# analog_heteroThermistor_3xChannel_R3.net
KiCad netlist of a schematic drawn in EAGLE
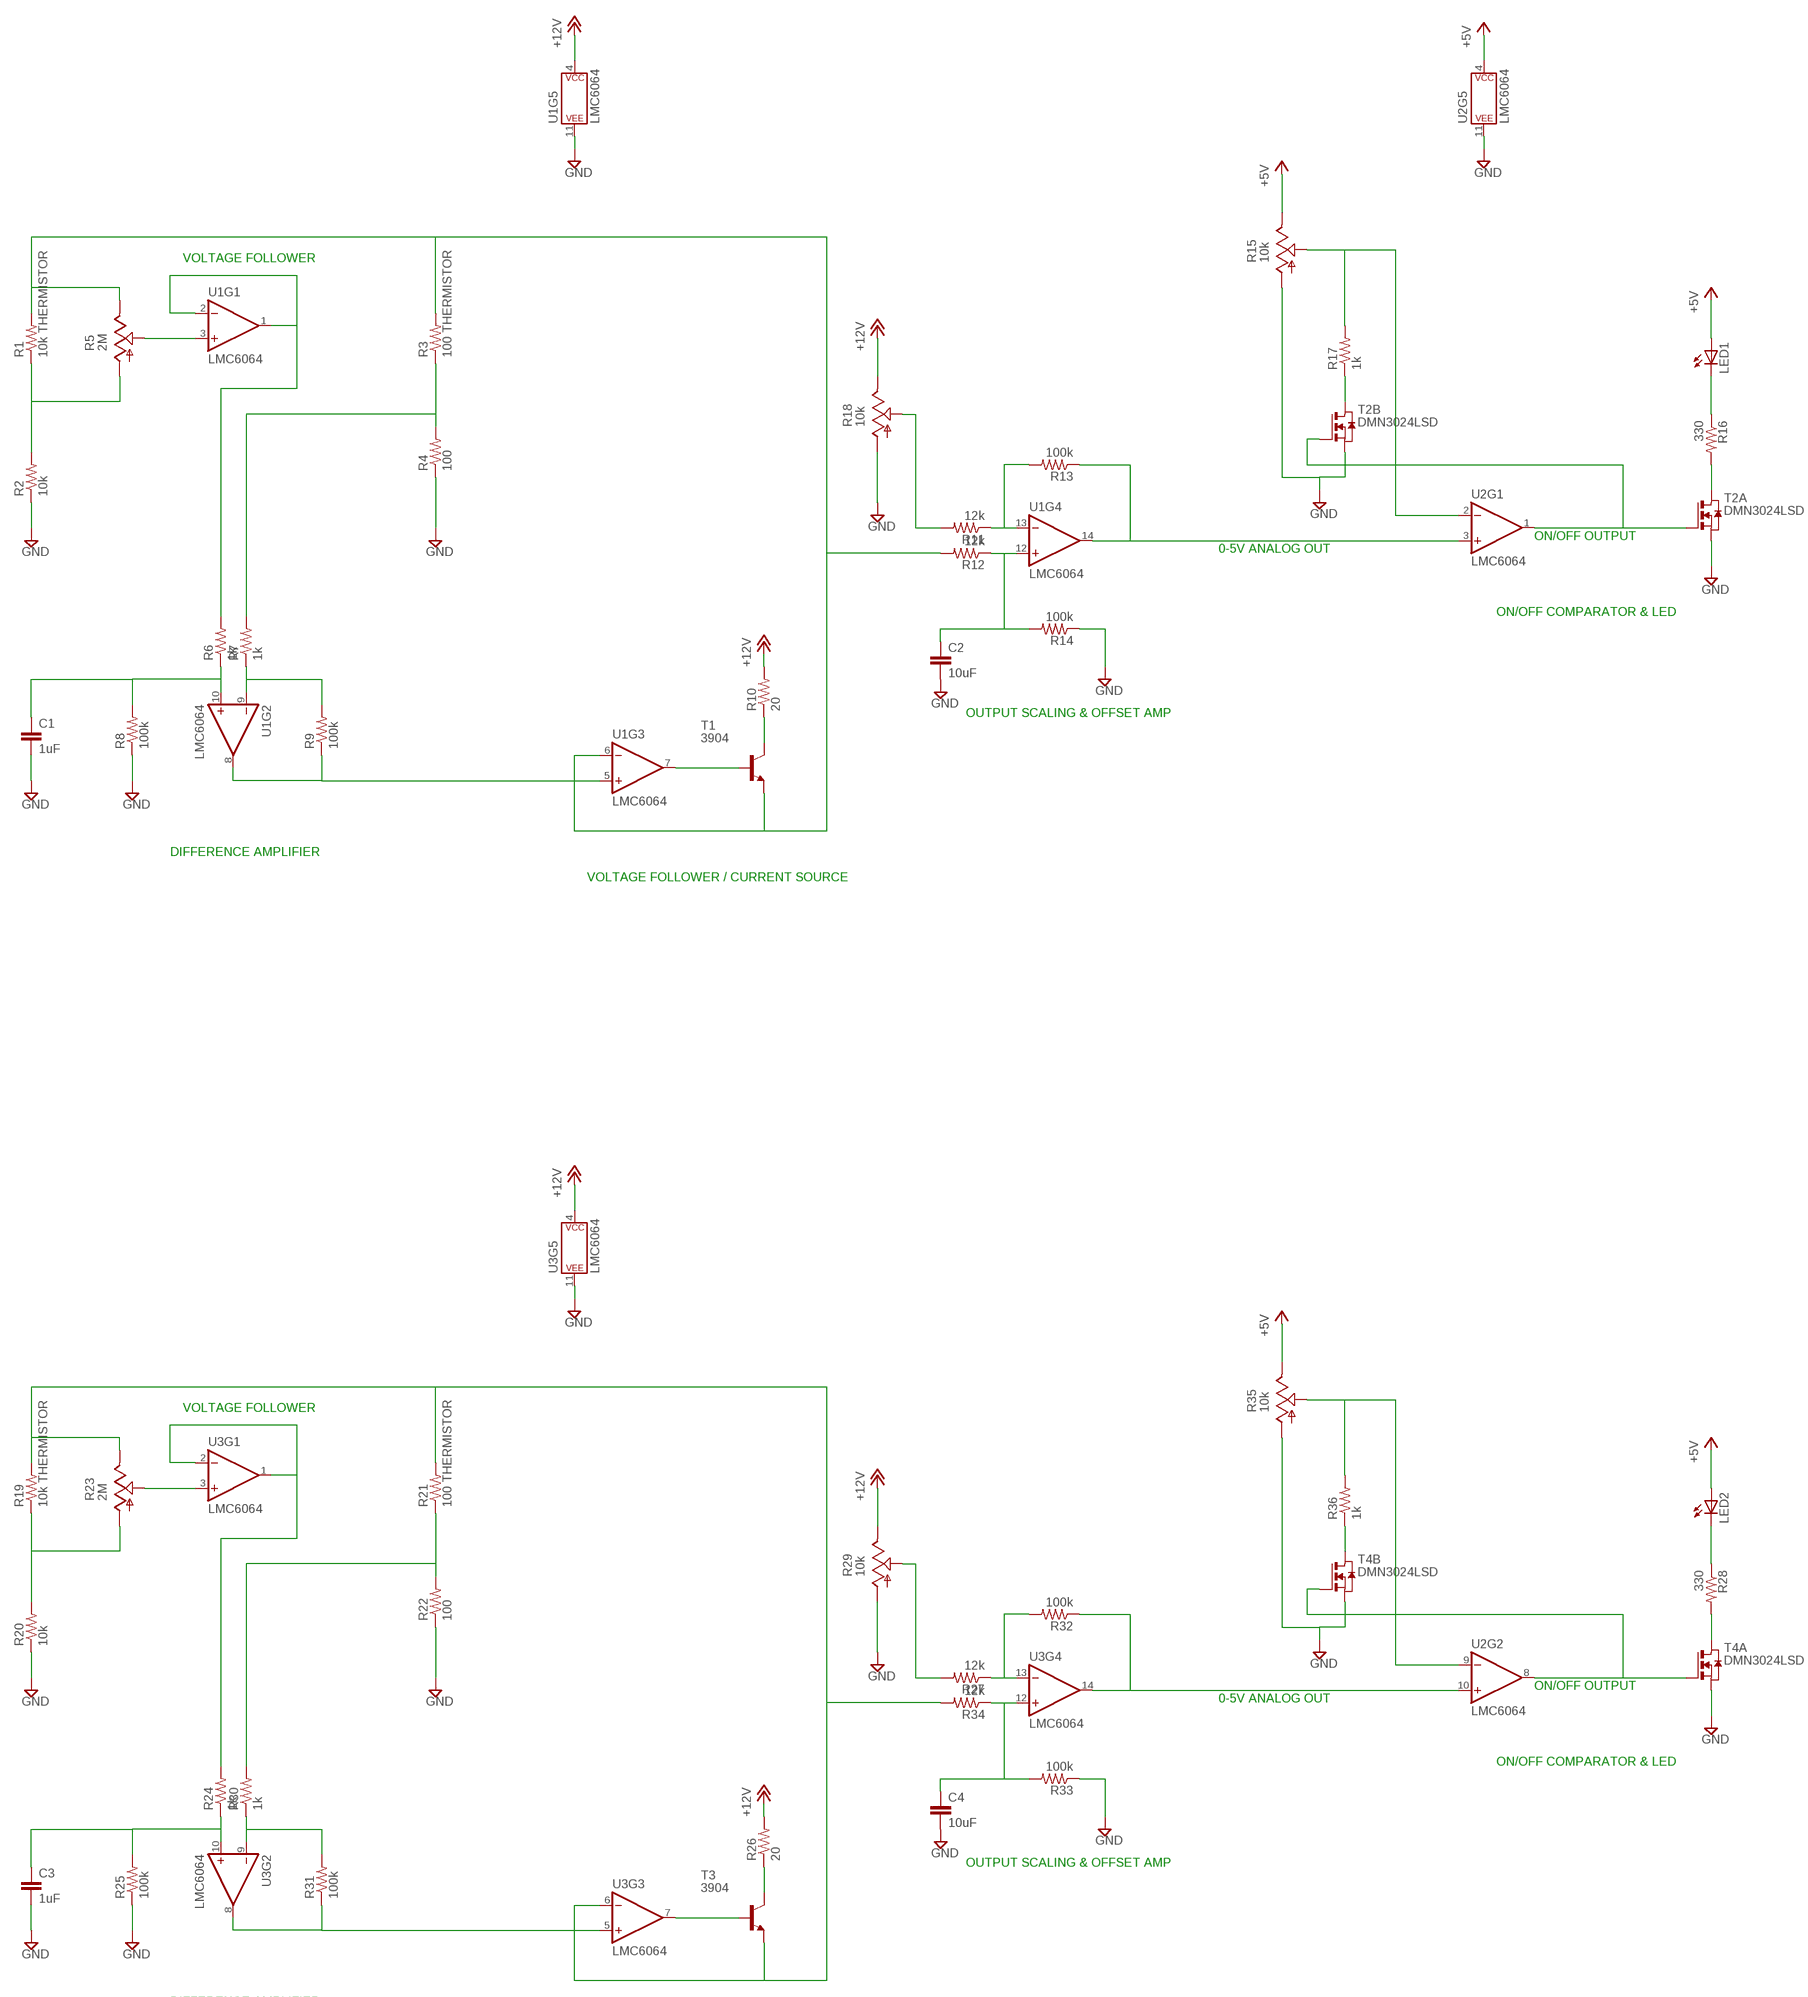
[diagram p0: schematic, sheet 1, part 1 of 2]
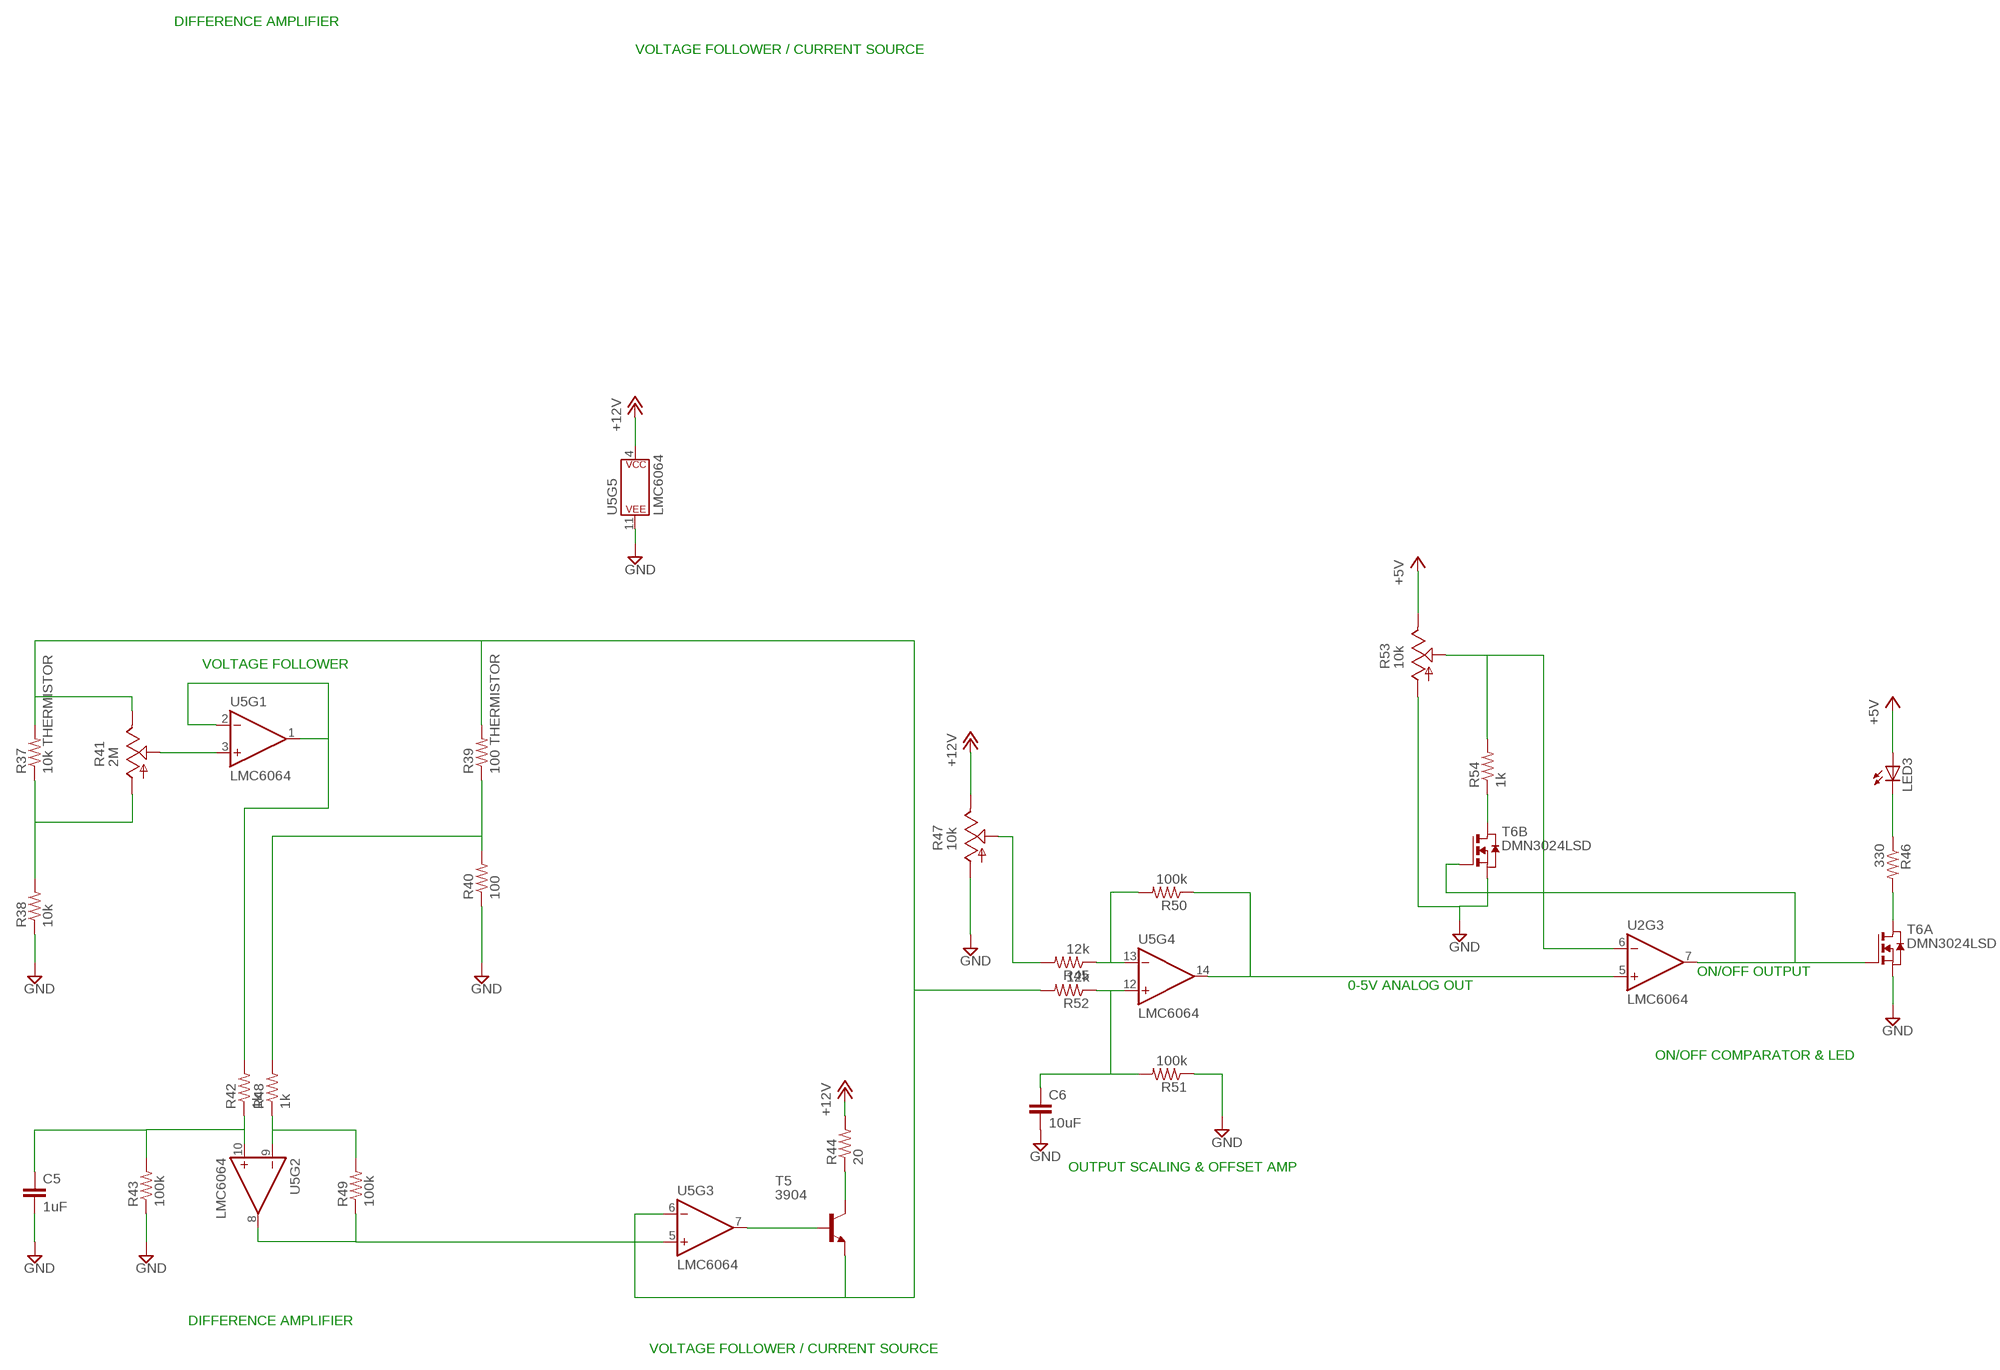
[diagram p1: schematic, sheet 1, part 2 of 2]

(export (version "E")
  (design (tool "Eeschema 10.0.6"))
  (components
    (comp (ref "C1")
      (value "1uF")
      (footprint "eagle-import:C0603")
      (fields
        (field (name "MF") "Murata Electronics North America")
        (field (name "MPN") "GRM188R61C105KA93D")
      )
      (libsource (lib "eagle-import") (part "C-EUC0603"))
    )
    (comp (ref "C2")
      (value "10uF")
      (footprint "eagle-import:C0603")
      (fields
        (field (name "MF") "Murata Electronics North America")
        (field (name "MPN") "GRM188C81C106MA73D")
      )
      (libsource (lib "eagle-import") (part "C-EUC0603"))
    )
    (comp (ref "C3")
      (value "1uF")
      (footprint "eagle-import:C0603")
      (fields
        (field (name "MF") "Murata Electronics North America")
        (field (name "MPN") "GRM188R61C105KA93D")
      )
      (libsource (lib "eagle-import") (part "C-EUC0603"))
    )
    (comp (ref "C4")
      (value "10uF")
      (footprint "eagle-import:C0603")
      (fields
        (field (name "MF") "Murata Electronics North America")
        (field (name "MPN") "GRM188C81C106MA73D")
      )
      (libsource (lib "eagle-import") (part "C-EUC0603"))
    )
    (comp (ref "C5")
      (value "1uF")
      (footprint "eagle-import:C0603")
      (fields
        (field (name "MF") "Murata Electronics North America")
        (field (name "MPN") "GRM188R61C105KA93D")
      )
      (libsource (lib "eagle-import") (part "C-EUC0603"))
    )
    (comp (ref "C6")
      (value "10uF")
      (footprint "eagle-import:C0603")
      (fields
        (field (name "MF") "Murata Electronics North America")
        (field (name "MPN") "GRM188C81C106MA73D")
      )
      (libsource (lib "eagle-import") (part "C-EUC0603"))
    )
    (comp (ref "LED1")
      (value "LEDCHIPLED_1206")
      (footprint "eagle-import:CHIPLED_1206")
      (fields (field (name "MF") "Lite-On Inc.") (field (name "MPN") "LTST-C150GKT"))
      (libsource (lib "eagle-import") (part "LEDCHIPLED_1206"))
    )
    (comp (ref "LED2")
      (value "LEDCHIPLED_1206")
      (footprint "eagle-import:CHIPLED_1206")
      (fields (field (name "MF") "Lite-On Inc.") (field (name "MPN") "LTST-C150GKT"))
      (libsource (lib "eagle-import") (part "LEDCHIPLED_1206"))
    )
    (comp (ref "LED3")
      (value "LEDCHIPLED_1206")
      (footprint "eagle-import:CHIPLED_1206")
      (fields (field (name "MF") "Lite-On Inc.") (field (name "MPN") "LTST-C150GKT"))
      (libsource (lib "eagle-import") (part "LEDCHIPLED_1206"))
    )
    (comp (ref "R1")
      (value "10k THERMISTOR")
      (footprint "eagle-import:R0603")
      (fields
        (field (name "DISTR") "Digikey")
        (field (name "DISTRPN") "490-2436-1-ND")
        (field (name "MF") "Murata Electronics North America")
        (field (name "MPN") "NCP18XH103J03RB")
      )
      (libsource (lib "eagle-import") (part "R-US_R0603"))
    )
    (comp (ref "R2")
      (value "10k")
      (footprint "eagle-import:R0603")
      (fields (field (name "MF") "Panasonic Electronic Components") (field (name "MPN") "ERJ-PA3F1002V"))
      (libsource (lib "eagle-import") (part "R-US_R0603"))
    )
    (comp (ref "R3")
      (value "100 THERMISTOR")
      (footprint "eagle-import:R0603")
      (fields
        (field (name "DISTR") "Digikey")
        (field (name "DISTRPN") "490-2434-1-ND")
        (field (name "MF") "Murata Electronics North America")
        (field (name "MPN") "NCP18XF101J03RB")
      )
      (libsource (lib "eagle-import") (part "R-US_R0603"))
    )
    (comp (ref "R4")
      (value "100")
      (footprint "eagle-import:R0603")
      (fields (field (name "MF") "Panasonic Electronic Components") (field (name "MPN") "ERJ-PA3F1000V"))
      (libsource (lib "eagle-import") (part "R-US_R0603"))
    )
    (comp (ref "R5")
      (value "2M")
      (footprint "eagle-import:SM-42_43W")
      (fields (field (name "MF") "Copal Electronics Inc.") (field (name "MPN") "SM-42TW205"))
      (libsource (lib "eagle-import") (part "TRIM_US-SM-42/43W"))
    )
    (comp (ref "R6")
      (value "1k")
      (footprint "eagle-import:R0603")
      (fields (field (name "MF") "Panasonic Electronic Components") (field (name "MPN") "ERJ-PA3F1001V"))
      (libsource (lib "eagle-import") (part "R-US_R0603"))
    )
    (comp (ref "R7")
      (value "1k")
      (footprint "eagle-import:R0603")
      (fields (field (name "MF") "Panasonic Electronic Components") (field (name "MPN") "ERJ-PA3F1001V"))
      (libsource (lib "eagle-import") (part "R-US_R0603"))
    )
    (comp (ref "R8")
      (value "100k")
      (footprint "eagle-import:R0603")
      (fields (field (name "MF") "Panasonic Electronic Components") (field (name "MPN") "ERJ-PA3F1003V"))
      (libsource (lib "eagle-import") (part "R-US_R0603"))
    )
    (comp (ref "R9")
      (value "100k")
      (footprint "eagle-import:R0603")
      (fields (field (name "MF") "Panasonic Electronic Components") (field (name "MPN") "ERJ-PA3F1003V"))
      (libsource (lib "eagle-import") (part "R-US_R0603"))
    )
    (comp (ref "R10")
      (value "20")
      (footprint "eagle-import:R0603")
      (fields (field (name "MF") "Panasonic Electronic Components") (field (name "MPN") "ERJ-PA3F20R0V"))
      (libsource (lib "eagle-import") (part "R-US_R0603"))
    )
    (comp (ref "R11")
      (value "12k")
      (footprint "eagle-import:R0603")
      (fields (field (name "MF") "Panasonic Electronic Components") (field (name "MPN") "ERJ-PA3F1202V"))
      (libsource (lib "eagle-import") (part "R-US_R0603"))
    )
    (comp (ref "R12")
      (value "12k")
      (footprint "eagle-import:R0603")
      (fields (field (name "MF") "Panasonic Electronic Components") (field (name "MPN") "ERJ-PA3F1202V"))
      (libsource (lib "eagle-import") (part "R-US_R0603"))
    )
    (comp (ref "R13")
      (value "100k")
      (footprint "eagle-import:R0603")
      (fields (field (name "MF") "Panasonic Electronic Components") (field (name "MPN") "ERJ-PA3F1003V"))
      (libsource (lib "eagle-import") (part "R-US_R0603"))
    )
    (comp (ref "R14")
      (value "100k")
      (footprint "eagle-import:R0603")
      (fields (field (name "MF") "Panasonic Electronic Components") (field (name "MPN") "ERJ-PA3F1003V"))
      (libsource (lib "eagle-import") (part "R-US_R0603"))
    )
    (comp (ref "R15")
      (value "10k")
      (footprint "eagle-import:SM-42_43W")
      (fields (field (name "MF") "Copal Electronics Inc.") (field (name "MPN") "SM-42TW103"))
      (libsource (lib "eagle-import") (part "TRIM_US-SM-42/43W"))
    )
    (comp (ref "R16")
      (value "330")
      (footprint "eagle-import:R0603")
      (fields (field (name "MF") "Panasonic Electronic Components") (field (name "MPN") "ERJ-PA3F3300V"))
      (libsource (lib "eagle-import") (part "R-US_R0603"))
    )
    (comp (ref "R17")
      (value "1k")
      (footprint "eagle-import:R0603")
      (fields (field (name "MF") "Panasonic Electronic Components") (field (name "MPN") "ERJ-PA3F1001V"))
      (libsource (lib "eagle-import") (part "R-US_R0603"))
    )
    (comp (ref "R18")
      (value "10k")
      (footprint "eagle-import:SM-42_43W")
      (fields (field (name "MF") "Copal Electronics Inc.") (field (name "MPN") "SM-42TW103"))
      (libsource (lib "eagle-import") (part "TRIM_US-SM-42/43W"))
    )
    (comp (ref "R19")
      (value "10k THERMISTOR")
      (footprint "eagle-import:R0603")
      (fields
        (field (name "DISTR") "Digikey")
        (field (name "DISTRPN") "490-2436-1-ND")
        (field (name "MF") "Murata Electronics North America")
        (field (name "MPN") "NCP18XH103J03RB")
      )
      (libsource (lib "eagle-import") (part "R-US_R0603"))
    )
    (comp (ref "R20")
      (value "10k")
      (footprint "eagle-import:R0603")
      (fields (field (name "MF") "Panasonic Electronic Components") (field (name "MPN") "ERJ-PA3F1002V"))
      (libsource (lib "eagle-import") (part "R-US_R0603"))
    )
    (comp (ref "R21")
      (value "100 THERMISTOR")
      (footprint "eagle-import:R0603")
      (fields
        (field (name "DISTR") "Digikey")
        (field (name "DISTRPN") "490-2434-1-ND")
        (field (name "MF") "Murata Electronics North America")
        (field (name "MPN") "NCP18XF101J03RB")
      )
      (libsource (lib "eagle-import") (part "R-US_R0603"))
    )
    (comp (ref "R22")
      (value "100")
      (footprint "eagle-import:R0603")
      (fields (field (name "MF") "Panasonic Electronic Components") (field (name "MPN") "ERJ-PA3F1000V"))
      (libsource (lib "eagle-import") (part "R-US_R0603"))
    )
    (comp (ref "R23")
      (value "2M")
      (footprint "eagle-import:SM-42_43W")
      (fields (field (name "MF") "Copal Electronics Inc.") (field (name "MPN") "SM-42TW205"))
      (libsource (lib "eagle-import") (part "TRIM_US-SM-42/43W"))
    )
    (comp (ref "R24")
      (value "1k")
      (footprint "eagle-import:R0603")
      (fields (field (name "MF") "Panasonic Electronic Components") (field (name "MPN") "ERJ-PA3F1001V"))
      (libsource (lib "eagle-import") (part "R-US_R0603"))
    )
    (comp (ref "R25")
      (value "100k")
      (footprint "eagle-import:R0603")
      (fields (field (name "MF") "Panasonic Electronic Components") (field (name "MPN") "ERJ-PA3F1003V"))
      (libsource (lib "eagle-import") (part "R-US_R0603"))
    )
    (comp (ref "R26")
      (value "20")
      (footprint "eagle-import:R0603")
      (fields (field (name "MF") "Panasonic Electronic Components") (field (name "MPN") "ERJ-PA3F20R0V"))
      (libsource (lib "eagle-import") (part "R-US_R0603"))
    )
    (comp (ref "R27")
      (value "12k")
      (footprint "eagle-import:R0603")
      (fields (field (name "MF") "Panasonic Electronic Components") (field (name "MPN") "ERJ-PA3F1202V"))
      (libsource (lib "eagle-import") (part "R-US_R0603"))
    )
    (comp (ref "R28")
      (value "330")
      (footprint "eagle-import:R0603")
      (fields (field (name "MF") "Panasonic Electronic Components") (field (name "MPN") "ERJ-PA3F3300V"))
      (libsource (lib "eagle-import") (part "R-US_R0603"))
    )
    (comp (ref "R29")
      (value "10k")
      (footprint "eagle-import:SM-42_43W")
      (fields (field (name "MF") "Copal Electronics Inc.") (field (name "MPN") "SM-42TW103"))
      (libsource (lib "eagle-import") (part "TRIM_US-SM-42/43W"))
    )
    (comp (ref "R30")
      (value "1k")
      (footprint "eagle-import:R0603")
      (fields (field (name "MF") "Panasonic Electronic Components") (field (name "MPN") "ERJ-PA3F1001V"))
      (libsource (lib "eagle-import") (part "R-US_R0603"))
    )
    (comp (ref "R31")
      (value "100k")
      (footprint "eagle-import:R0603")
      (fields (field (name "MF") "Panasonic Electronic Components") (field (name "MPN") "ERJ-PA3F1003V"))
      (libsource (lib "eagle-import") (part "R-US_R0603"))
    )
    (comp (ref "R32")
      (value "100k")
      (footprint "eagle-import:R0603")
      (fields (field (name "MF") "Panasonic Electronic Components") (field (name "MPN") "ERJ-PA3F1003V"))
      (libsource (lib "eagle-import") (part "R-US_R0603"))
    )
    (comp (ref "R33")
      (value "100k")
      (footprint "eagle-import:R0603")
      (fields (field (name "MF") "Panasonic Electronic Components") (field (name "MPN") "ERJ-PA3F1003V"))
      (libsource (lib "eagle-import") (part "R-US_R0603"))
    )
    (comp (ref "R34")
      (value "12k")
      (footprint "eagle-import:R0603")
      (fields (field (name "MF") "Panasonic Electronic Components") (field (name "MPN") "ERJ-PA3F1202V"))
      (libsource (lib "eagle-import") (part "R-US_R0603"))
    )
    (comp (ref "R35")
      (value "10k")
      (footprint "eagle-import:SM-42_43W")
      (fields (field (name "MF") "Copal Electronics Inc.") (field (name "MPN") "SM-42TW103"))
      (libsource (lib "eagle-import") (part "TRIM_US-SM-42/43W"))
    )
    (comp (ref "R36")
      (value "1k")
      (footprint "eagle-import:R0603")
      (fields (field (name "MF") "Panasonic Electronic Components") (field (name "MPN") "ERJ-PA3F1001V"))
      (libsource (lib "eagle-import") (part "R-US_R0603"))
    )
    (comp (ref "R37")
      (value "10k THERMISTOR")
      (footprint "eagle-import:R0603")
      (fields
        (field (name "DISTR") "Digikey")
        (field (name "DISTRPN") "490-2436-1-ND")
        (field (name "MF") "Murata Electronics North America")
        (field (name "MPN") "NCP18XH103J03RB")
      )
      (libsource (lib "eagle-import") (part "R-US_R0603"))
    )
    (comp (ref "R38")
      (value "10k")
      (footprint "eagle-import:R0603")
      (fields (field (name "MF") "Panasonic Electronic Components") (field (name "MPN") "ERJ-PA3F1002V"))
      (libsource (lib "eagle-import") (part "R-US_R0603"))
    )
    (comp (ref "R39")
      (value "100 THERMISTOR")
      (footprint "eagle-import:R0603")
      (fields
        (field (name "DISTR") "Digikey")
        (field (name "DISTRPN") "490-2434-1-ND")
        (field (name "MF") "Murata Electronics North America")
        (field (name "MPN") "NCP18XF101J03RB")
      )
      (libsource (lib "eagle-import") (part "R-US_R0603"))
    )
    (comp (ref "R40")
      (value "100")
      (footprint "eagle-import:R0603")
      (fields (field (name "MF") "Panasonic Electronic Components") (field (name "MPN") "ERJ-PA3F1000V"))
      (libsource (lib "eagle-import") (part "R-US_R0603"))
    )
    (comp (ref "R41")
      (value "2M")
      (footprint "eagle-import:SM-42_43W")
      (fields (field (name "MF") "Copal Electronics Inc.") (field (name "MPN") "SM-42TW205"))
      (libsource (lib "eagle-import") (part "TRIM_US-SM-42/43W"))
    )
    (comp (ref "R42")
      (value "1k")
      (footprint "eagle-import:R0603")
      (fields (field (name "MF") "Panasonic Electronic Components") (field (name "MPN") "ERJ-PA3F1001V"))
      (libsource (lib "eagle-import") (part "R-US_R0603"))
    )
    (comp (ref "R43")
      (value "100k")
      (footprint "eagle-import:R0603")
      (fields (field (name "MF") "Panasonic Electronic Components") (field (name "MPN") "ERJ-PA3F1003V"))
      (libsource (lib "eagle-import") (part "R-US_R0603"))
    )
    (comp (ref "R44")
      (value "20")
      (footprint "eagle-import:R0603")
      (fields (field (name "MF") "Panasonic Electronic Components") (field (name "MPN") "ERJ-PA3F20R0V"))
      (libsource (lib "eagle-import") (part "R-US_R0603"))
    )
    (comp (ref "R45")
      (value "12k")
      (footprint "eagle-import:R0603")
      (fields (field (name "MF") "Panasonic Electronic Components") (field (name "MPN") "ERJ-PA3F1202V"))
      (libsource (lib "eagle-import") (part "R-US_R0603"))
    )
    (comp (ref "R46")
      (value "330")
      (footprint "eagle-import:R0603")
      (fields (field (name "MF") "Panasonic Electronic Components") (field (name "MPN") "ERJ-PA3F3300V"))
      (libsource (lib "eagle-import") (part "R-US_R0603"))
    )
    (comp (ref "R47")
      (value "10k")
      (footprint "eagle-import:SM-42_43W")
      (fields (field (name "MF") "Copal Electronics Inc.") (field (name "MPN") "SM-42TW103"))
      (libsource (lib "eagle-import") (part "TRIM_US-SM-42/43W"))
    )
    (comp (ref "R48")
      (value "1k")
      (footprint "eagle-import:R0603")
      (fields (field (name "MF") "Panasonic Electronic Components") (field (name "MPN") "ERJ-PA3F1001V"))
      (libsource (lib "eagle-import") (part "R-US_R0603"))
    )
    (comp (ref "R49")
      (value "100k")
      (footprint "eagle-import:R0603")
      (fields (field (name "MF") "Panasonic Electronic Components") (field (name "MPN") "ERJ-PA3F1003V"))
      (libsource (lib "eagle-import") (part "R-US_R0603"))
    )
    (comp (ref "R50")
      (value "100k")
      (footprint "eagle-import:R0603")
      (fields (field (name "MF") "Panasonic Electronic Components") (field (name "MPN") "ERJ-PA3F1003V"))
      (libsource (lib "eagle-import") (part "R-US_R0603"))
    )
    (comp (ref "R51")
      (value "100k")
      (footprint "eagle-import:R0603")
      (fields (field (name "MF") "Panasonic Electronic Components") (field (name "MPN") "ERJ-PA3F1003V"))
      (libsource (lib "eagle-import") (part "R-US_R0603"))
    )
    (comp (ref "R52")
      (value "12k")
      (footprint "eagle-import:R0603")
      (fields (field (name "MF") "Panasonic Electronic Components") (field (name "MPN") "ERJ-PA3F1202V"))
      (libsource (lib "eagle-import") (part "R-US_R0603"))
    )
    (comp (ref "R53")
      (value "10k")
      (footprint "eagle-import:SM-42_43W")
      (fields (field (name "MF") "Copal Electronics Inc.") (field (name "MPN") "SM-42TW103"))
      (libsource (lib "eagle-import") (part "TRIM_US-SM-42/43W"))
    )
    (comp (ref "R54")
      (value "1k")
      (footprint "eagle-import:R0603")
      (fields (field (name "MF") "Panasonic Electronic Components") (field (name "MPN") "ERJ-PA3F1001V"))
      (libsource (lib "eagle-import") (part "R-US_R0603"))
    )
    (comp (ref "T1")
      (value "3904")
      (footprint "eagle-import:SOT23-BEC")
      (fields (field (name "MF") "Fairchild/ON Semiconductor") (field (name "MPN") "MMBT3904"))
      (libsource (lib "eagle-import") (part "-NPN-SOT23-BECMMBT3904LT1"))
    )
    (comp (ref "T2")
      (value "DMN3024LSD")
      (footprint "eagle-import:SO8")
      (fields
        (field (name "MF") "Diodes Incorporated")
        (field (name "MPN") "DMN3024LSD-13")
        (field (name "DISTR") "Digikey")
        (field (name "DISTRPN") "DMN3024LSD-13DICT-ND")
      )
      (libsource (lib "eagle-import") (part "DMN3024LSD"))
    )
    (comp (ref "T3")
      (value "3904")
      (footprint "eagle-import:SOT23-BEC")
      (fields (field (name "MF") "Fairchild/ON Semiconductor") (field (name "MPN") "MMBT3904"))
      (libsource (lib "eagle-import") (part "-NPN-SOT23-BECMMBT3904LT1"))
    )
    (comp (ref "T4")
      (value "DMN3024LSD")
      (footprint "eagle-import:SO8")
      (fields
        (field (name "MF") "Diodes Incorporated")
        (field (name "MPN") "DMN3024LSD-13")
        (field (name "DISTR") "Digikey")
        (field (name "DISTRPN") "DMN3024LSD-13DICT-ND")
      )
      (libsource (lib "eagle-import") (part "DMN3024LSD"))
    )
    (comp (ref "T5")
      (value "3904")
      (footprint "eagle-import:SOT23-BEC")
      (fields (field (name "MF") "Fairchild/ON Semiconductor") (field (name "MPN") "MMBT3904"))
      (libsource (lib "eagle-import") (part "-NPN-SOT23-BECMMBT3904LT1"))
    )
    (comp (ref "T6")
      (value "DMN3024LSD")
      (footprint "eagle-import:SO8")
      (fields
        (field (name "MF") "Diodes Incorporated")
        (field (name "MPN") "DMN3024LSD-13")
        (field (name "DISTR") "Digikey")
        (field (name "DISTRPN") "DMN3024LSD-13DICT-ND")
      )
      (libsource (lib "eagle-import") (part "DMN3024LSD"))
    )
    (comp (ref "U1")
      (value "LMC6064")
      (footprint "eagle-import:SO14")
      (fields
        (field (name "DISTR") "Digikey")
        (field (name "DISTRPN") "296-35438-1-ND")
        (field (name "MF") "Texas Instruments")
        (field (name "MPN") "LMC6064AIMX/NOPB")
      )
      (libsource (lib "eagle-import") (part "LMC6064"))
    )
    (comp (ref "U2")
      (value "LMC6064")
      (footprint "eagle-import:SO14")
      (fields
        (field (name "DISTR") "Digikey")
        (field (name "DISTRPN") "296-35438-1-ND")
        (field (name "MF") "Texas Instruments")
        (field (name "MPN") "LMC6064AIMX/NOPB")
      )
      (libsource (lib "eagle-import") (part "LMC6064"))
    )
    (comp (ref "U3")
      (value "LMC6064")
      (footprint "eagle-import:SO14")
      (fields
        (field (name "MF") "Texas Instruments")
        (field (name "MPN") "LMC6064AIMX/NOPB")
        (field (name "DISTR") "Digikey")
        (field (name "DISTRPN") "296-35438-1-ND")
      )
      (libsource (lib "eagle-import") (part "LMC6064"))
    )
    (comp (ref "U5")
      (value "LMC6064")
      (footprint "eagle-import:SO14")
      (fields
        (field (name "DISTR") "Digikey")
        (field (name "DISTRPN") "296-35438-1-ND")
        (field (name "MF") "Texas Instruments")
        (field (name "MPN") "LMC6064AIMX/NOPB")
      )
      (libsource (lib "eagle-import") (part "LMC6064"))
    )
  )
  (nets
    (net (code "1") (name "+5V") (class "Default")
      (node (ref "LED1") (pin "A") (pinfunction "A_A") (pintype "passive"))
      (node (ref "LED2") (pin "A") (pinfunction "A_A") (pintype "passive"))
      (node (ref "LED3") (pin "A") (pinfunction "A_A") (pintype "passive"))
      (node (ref "R15") (pin "3") (pinfunction "E_3") (pintype "passive"))
      (node (ref "R35") (pin "3") (pinfunction "E_3") (pintype "passive"))
      (node (ref "R53") (pin "3") (pinfunction "E_3") (pintype "passive"))
      (node (ref "U2") (pin "4") (pinfunction "P$V+_4") (pintype "bidirectional"))
    )
    (net (code "2") (name "+12V") (class "Default")
      (node (ref "R10") (pin "2") (pinfunction "2_2") (pintype "passive"))
      (node (ref "R18") (pin "3") (pinfunction "E_3") (pintype "passive"))
      (node (ref "R26") (pin "2") (pinfunction "2_2") (pintype "passive"))
      (node (ref "R29") (pin "3") (pinfunction "E_3") (pintype "passive"))
      (node (ref "R44") (pin "2") (pinfunction "2_2") (pintype "passive"))
      (node (ref "R47") (pin "3") (pinfunction "E_3") (pintype "passive"))
      (node (ref "U1") (pin "4") (pinfunction "P$V+_4") (pintype "bidirectional"))
      (node (ref "U3") (pin "4") (pinfunction "P$V+_4") (pintype "bidirectional"))
      (node (ref "U5") (pin "4") (pinfunction "P$V+_4") (pintype "bidirectional"))
    )
    (net (code "3") (name "GND") (class "Default")
      (node (ref "C1") (pin "2") (pinfunction "2_2") (pintype "passive"))
      (node (ref "C2") (pin "2") (pinfunction "2_2") (pintype "passive"))
      (node (ref "C3") (pin "2") (pinfunction "2_2") (pintype "passive"))
      (node (ref "C4") (pin "2") (pinfunction "2_2") (pintype "passive"))
      (node (ref "C5") (pin "2") (pinfunction "2_2") (pintype "passive"))
      (node (ref "C6") (pin "2") (pinfunction "2_2") (pintype "passive"))
      (node (ref "R14") (pin "1") (pinfunction "1_1") (pintype "passive"))
      (node (ref "R15") (pin "1") (pinfunction "A_1") (pintype "passive"))
      (node (ref "R18") (pin "1") (pinfunction "A_1") (pintype "passive"))
      (node (ref "R2") (pin "1") (pinfunction "1_1") (pintype "passive"))
      (node (ref "R20") (pin "1") (pinfunction "1_1") (pintype "passive"))
      (node (ref "R22") (pin "1") (pinfunction "1_1") (pintype "passive"))
      (node (ref "R25") (pin "1") (pinfunction "1_1") (pintype "passive"))
      (node (ref "R29") (pin "1") (pinfunction "A_1") (pintype "passive"))
      (node (ref "R33") (pin "1") (pinfunction "1_1") (pintype "passive"))
      (node (ref "R35") (pin "1") (pinfunction "A_1") (pintype "passive"))
      (node (ref "R38") (pin "1") (pinfunction "1_1") (pintype "passive"))
      (node (ref "R4") (pin "1") (pinfunction "1_1") (pintype "passive"))
      (node (ref "R40") (pin "1") (pinfunction "1_1") (pintype "passive"))
      (node (ref "R43") (pin "1") (pinfunction "1_1") (pintype "passive"))
      (node (ref "R47") (pin "1") (pinfunction "A_1") (pintype "passive"))
      (node (ref "R51") (pin "1") (pinfunction "1_1") (pintype "passive"))
      (node (ref "R53") (pin "1") (pinfunction "A_1") (pintype "passive"))
      (node (ref "R8") (pin "1") (pinfunction "1_1") (pintype "passive"))
      (node (ref "T2") (pin "1") (pinfunction "S_1") (pintype "passive"))
      (node (ref "T2") (pin "3") (pinfunction "S_3") (pintype "passive"))
      (node (ref "T4") (pin "1") (pinfunction "S_1") (pintype "passive"))
      (node (ref "T4") (pin "3") (pinfunction "S_3") (pintype "passive"))
      (node (ref "T6") (pin "1") (pinfunction "S_1") (pintype "passive"))
      (node (ref "T6") (pin "3") (pinfunction "S_3") (pintype "passive"))
      (node (ref "U1") (pin "11") (pinfunction "P$V-_11") (pintype "bidirectional"))
      (node (ref "U2") (pin "11") (pinfunction "P$V-_11") (pintype "bidirectional"))
      (node (ref "U3") (pin "11") (pinfunction "P$V-_11") (pintype "bidirectional"))
      (node (ref "U5") (pin "11") (pinfunction "P$V-_11") (pintype "bidirectional"))
    )
    (net (code "4") (name "Net-(LED1-PadC)") (class "Default")
      (node (ref "LED1") (pin "C") (pinfunction "C_C") (pintype "passive"))
      (node (ref "R16") (pin "1") (pinfunction "1_1") (pintype "passive"))
    )
    (net (code "5") (name "Net-(LED2-PadC)") (class "Default")
      (node (ref "LED2") (pin "C") (pinfunction "C_C") (pintype "passive"))
      (node (ref "R28") (pin "1") (pinfunction "1_1") (pintype "passive"))
    )
    (net (code "6") (name "Net-(LED3-PadC)") (class "Default")
      (node (ref "LED3") (pin "C") (pinfunction "C_C") (pintype "passive"))
      (node (ref "R46") (pin "1") (pinfunction "1_1") (pintype "passive"))
    )
    (net (code "7") (name "Net-(R3-Pad1)") (class "Default")
      (node (ref "R3") (pin "1") (pinfunction "1_1") (pintype "passive"))
      (node (ref "R4") (pin "2") (pinfunction "2_2") (pintype "passive"))
      (node (ref "R7") (pin "2") (pinfunction "2_2") (pintype "passive"))
    )
    (net (code "8") (name "Net-(R5-A)") (class "Default")
      (node (ref "R1") (pin "1") (pinfunction "1_1") (pintype "passive"))
      (node (ref "R2") (pin "2") (pinfunction "2_2") (pintype "passive"))
      (node (ref "R5") (pin "1") (pinfunction "A_1") (pintype "passive"))
    )
    (net (code "9") (name "Net-(R5-E)") (class "Default")
      (node (ref "R1") (pin "2") (pinfunction "2_2") (pintype "passive"))
      (node (ref "R12") (pin "2") (pinfunction "2_2") (pintype "passive"))
      (node (ref "R3") (pin "2") (pinfunction "2_2") (pintype "passive"))
      (node (ref "R5") (pin "3") (pinfunction "E_3") (pintype "passive"))
      (node (ref "T1") (pin "E") (pinfunction "E_E") (pintype "passive"))
      (node (ref "U1") (pin "6") (pinfunction "-IN_6") (pintype "input"))
    )
    (net (code "10") (name "Net-(R5-S)") (class "Default")
      (node (ref "R5") (pin "2") (pinfunction "S_2") (pintype "passive"))
      (node (ref "U1") (pin "3") (pinfunction "+IN_3") (pintype "input"))
    )
    (net (code "11") (name "Net-(R10-Pad1)") (class "Default")
      (node (ref "R10") (pin "1") (pinfunction "1_1") (pintype "passive"))
      (node (ref "T1") (pin "C") (pinfunction "C_C") (pintype "passive"))
    )
    (net (code "12") (name "Net-(R15-S)") (class "Default")
      (node (ref "R15") (pin "2") (pinfunction "S_2") (pintype "passive"))
      (node (ref "R17") (pin "2") (pinfunction "2_2") (pintype "passive"))
      (node (ref "U2") (pin "2") (pinfunction "-IN_2") (pintype "input"))
    )
    (net (code "13") (name "Net-(R16-Pad2)") (class "Default")
      (node (ref "R16") (pin "2") (pinfunction "2_2") (pintype "passive"))
      (node (ref "T2") (pin "7") (pinfunction "D_7") (pintype "passive"))
      (node (ref "T2") (pin "8") (pinfunction "D_8") (pintype "passive"))
    )
    (net (code "14") (name "Net-(R17-Pad1)") (class "Default")
      (node (ref "R17") (pin "1") (pinfunction "1_1") (pintype "passive"))
      (node (ref "T2") (pin "5") (pinfunction "D_5") (pintype "passive"))
      (node (ref "T2") (pin "6") (pinfunction "D_6") (pintype "passive"))
    )
    (net (code "15") (name "Net-(R18-S)") (class "Default")
      (node (ref "R11") (pin "2") (pinfunction "2_2") (pintype "passive"))
      (node (ref "R18") (pin "2") (pinfunction "S_2") (pintype "passive"))
    )
    (net (code "16") (name "Net-(R21-Pad1)") (class "Default")
      (node (ref "R21") (pin "1") (pinfunction "1_1") (pintype "passive"))
      (node (ref "R22") (pin "2") (pinfunction "2_2") (pintype "passive"))
      (node (ref "R30") (pin "2") (pinfunction "2_2") (pintype "passive"))
    )
    (net (code "17") (name "Net-(R23-A)") (class "Default")
      (node (ref "R19") (pin "1") (pinfunction "1_1") (pintype "passive"))
      (node (ref "R20") (pin "2") (pinfunction "2_2") (pintype "passive"))
      (node (ref "R23") (pin "1") (pinfunction "A_1") (pintype "passive"))
    )
    (net (code "18") (name "Net-(R23-E)") (class "Default")
      (node (ref "R19") (pin "2") (pinfunction "2_2") (pintype "passive"))
      (node (ref "R21") (pin "2") (pinfunction "2_2") (pintype "passive"))
      (node (ref "R23") (pin "3") (pinfunction "E_3") (pintype "passive"))
      (node (ref "R34") (pin "2") (pinfunction "2_2") (pintype "passive"))
      (node (ref "T3") (pin "E") (pinfunction "E_E") (pintype "passive"))
      (node (ref "U3") (pin "6") (pinfunction "-IN_6") (pintype "input"))
    )
    (net (code "19") (name "Net-(R23-S)") (class "Default")
      (node (ref "R23") (pin "2") (pinfunction "S_2") (pintype "passive"))
      (node (ref "U3") (pin "3") (pinfunction "+IN_3") (pintype "input"))
    )
    (net (code "20") (name "Net-(R26-Pad1)") (class "Default")
      (node (ref "R26") (pin "1") (pinfunction "1_1") (pintype "passive"))
      (node (ref "T3") (pin "C") (pinfunction "C_C") (pintype "passive"))
    )
    (net (code "21") (name "Net-(R28-Pad2)") (class "Default")
      (node (ref "R28") (pin "2") (pinfunction "2_2") (pintype "passive"))
      (node (ref "T4") (pin "7") (pinfunction "D_7") (pintype "passive"))
      (node (ref "T4") (pin "8") (pinfunction "D_8") (pintype "passive"))
    )
    (net (code "22") (name "Net-(R29-S)") (class "Default")
      (node (ref "R27") (pin "2") (pinfunction "2_2") (pintype "passive"))
      (node (ref "R29") (pin "2") (pinfunction "S_2") (pintype "passive"))
    )
    (net (code "23") (name "Net-(R35-S)") (class "Default")
      (node (ref "R35") (pin "2") (pinfunction "S_2") (pintype "passive"))
      (node (ref "R36") (pin "2") (pinfunction "2_2") (pintype "passive"))
      (node (ref "U2") (pin "9") (pinfunction "-IN_9") (pintype "input"))
    )
    (net (code "24") (name "Net-(R36-Pad1)") (class "Default")
      (node (ref "R36") (pin "1") (pinfunction "1_1") (pintype "passive"))
      (node (ref "T4") (pin "5") (pinfunction "D_5") (pintype "passive"))
      (node (ref "T4") (pin "6") (pinfunction "D_6") (pintype "passive"))
    )
    (net (code "25") (name "Net-(R39-Pad1)") (class "Default")
      (node (ref "R39") (pin "1") (pinfunction "1_1") (pintype "passive"))
      (node (ref "R40") (pin "2") (pinfunction "2_2") (pintype "passive"))
      (node (ref "R48") (pin "2") (pinfunction "2_2") (pintype "passive"))
    )
    (net (code "26") (name "Net-(R41-A)") (class "Default")
      (node (ref "R37") (pin "1") (pinfunction "1_1") (pintype "passive"))
      (node (ref "R38") (pin "2") (pinfunction "2_2") (pintype "passive"))
      (node (ref "R41") (pin "1") (pinfunction "A_1") (pintype "passive"))
    )
    (net (code "27") (name "Net-(R41-E)") (class "Default")
      (node (ref "R37") (pin "2") (pinfunction "2_2") (pintype "passive"))
      (node (ref "R39") (pin "2") (pinfunction "2_2") (pintype "passive"))
      (node (ref "R41") (pin "3") (pinfunction "E_3") (pintype "passive"))
      (node (ref "R52") (pin "2") (pinfunction "2_2") (pintype "passive"))
      (node (ref "T5") (pin "E") (pinfunction "E_E") (pintype "passive"))
      (node (ref "U5") (pin "6") (pinfunction "-IN_6") (pintype "input"))
    )
    (net (code "28") (name "Net-(R41-S)") (class "Default")
      (node (ref "R41") (pin "2") (pinfunction "S_2") (pintype "passive"))
      (node (ref "U5") (pin "3") (pinfunction "+IN_3") (pintype "input"))
    )
    (net (code "29") (name "Net-(R44-Pad1)") (class "Default")
      (node (ref "R44") (pin "1") (pinfunction "1_1") (pintype "passive"))
      (node (ref "T5") (pin "C") (pinfunction "C_C") (pintype "passive"))
    )
    (net (code "30") (name "Net-(R46-Pad2)") (class "Default")
      (node (ref "R46") (pin "2") (pinfunction "2_2") (pintype "passive"))
      (node (ref "T6") (pin "7") (pinfunction "D_7") (pintype "passive"))
      (node (ref "T6") (pin "8") (pinfunction "D_8") (pintype "passive"))
    )
    (net (code "31") (name "Net-(R47-S)") (class "Default")
      (node (ref "R45") (pin "2") (pinfunction "2_2") (pintype "passive"))
      (node (ref "R47") (pin "2") (pinfunction "S_2") (pintype "passive"))
    )
    (net (code "32") (name "Net-(R53-S)") (class "Default")
      (node (ref "R53") (pin "2") (pinfunction "S_2") (pintype "passive"))
      (node (ref "R54") (pin "2") (pinfunction "2_2") (pintype "passive"))
      (node (ref "U2") (pin "6") (pinfunction "-IN_6") (pintype "input"))
    )
    (net (code "33") (name "Net-(R54-Pad1)") (class "Default")
      (node (ref "R54") (pin "1") (pinfunction "1_1") (pintype "passive"))
      (node (ref "T6") (pin "5") (pinfunction "D_5") (pintype "passive"))
      (node (ref "T6") (pin "6") (pinfunction "D_6") (pintype "passive"))
    )
    (net (code "34") (name "Net-(T2A-G)") (class "Default")
      (node (ref "T2") (pin "2") (pinfunction "G_2") (pintype "passive"))
      (node (ref "T2") (pin "4") (pinfunction "G_4") (pintype "passive"))
      (node (ref "U2") (pin "1") (pinfunction "OUT_1") (pintype "output"))
    )
    (net (code "35") (name "Net-(T4A-G)") (class "Default")
      (node (ref "T4") (pin "2") (pinfunction "G_2") (pintype "passive"))
      (node (ref "T4") (pin "4") (pinfunction "G_4") (pintype "passive"))
      (node (ref "U2") (pin "8") (pinfunction "OUT_8") (pintype "output"))
    )
    (net (code "36") (name "Net-(T6A-G)") (class "Default")
      (node (ref "T6") (pin "2") (pinfunction "G_2") (pintype "passive"))
      (node (ref "T6") (pin "4") (pinfunction "G_4") (pintype "passive"))
      (node (ref "U2") (pin "7") (pinfunction "OUT_7") (pintype "output"))
    )
    (net (code "37") (name "Net-(U1A--IN)") (class "Default")
      (node (ref "R6") (pin "2") (pinfunction "2_2") (pintype "passive"))
      (node (ref "U1") (pin "1") (pinfunction "OUT_1") (pintype "output"))
      (node (ref "U1") (pin "2") (pinfunction "-IN_2") (pintype "input"))
    )
    (net (code "38") (name "Net-(U1B-+IN)") (class "Default")
      (node (ref "C1") (pin "1") (pinfunction "1_1") (pintype "passive"))
      (node (ref "R6") (pin "1") (pinfunction "1_1") (pintype "passive"))
      (node (ref "R8") (pin "2") (pinfunction "2_2") (pintype "passive"))
      (node (ref "U1") (pin "10") (pinfunction "+IN_10") (pintype "input"))
    )
    (net (code "39") (name "Net-(U1B--IN)") (class "Default")
      (node (ref "R7") (pin "1") (pinfunction "1_1") (pintype "passive"))
      (node (ref "R9") (pin "2") (pinfunction "2_2") (pintype "passive"))
      (node (ref "U1") (pin "9") (pinfunction "-IN_9") (pintype "input"))
    )
    (net (code "40") (name "Net-(U1B-OUT)") (class "Default")
      (node (ref "R9") (pin "1") (pinfunction "1_1") (pintype "passive"))
      (node (ref "U1") (pin "5") (pinfunction "+IN_5") (pintype "input"))
      (node (ref "U1") (pin "8") (pinfunction "OUT_8") (pintype "output"))
    )
    (net (code "41") (name "Net-(U1C-OUT)") (class "Default")
      (node (ref "T1") (pin "B") (pinfunction "B_B") (pintype "passive"))
      (node (ref "U1") (pin "7") (pinfunction "OUT_7") (pintype "output"))
    )
    (net (code "42") (name "Net-(U1D-+IN)") (class "Default")
      (node (ref "C2") (pin "1") (pinfunction "1_1") (pintype "passive"))
      (node (ref "R12") (pin "1") (pinfunction "1_1") (pintype "passive"))
      (node (ref "R14") (pin "2") (pinfunction "2_2") (pintype "passive"))
      (node (ref "U1") (pin "12") (pinfunction "+IN_12") (pintype "input"))
    )
    (net (code "43") (name "Net-(U1D--IN)") (class "Default")
      (node (ref "R11") (pin "1") (pinfunction "1_1") (pintype "passive"))
      (node (ref "R13") (pin "2") (pinfunction "2_2") (pintype "passive"))
      (node (ref "U1") (pin "13") (pinfunction "-IN_13") (pintype "input"))
    )
    (net (code "44") (name "Net-(U1D-OUT)") (class "Default")
      (node (ref "R13") (pin "1") (pinfunction "1_1") (pintype "passive"))
      (node (ref "U1") (pin "14") (pinfunction "OUT_14") (pintype "output"))
      (node (ref "U2") (pin "3") (pinfunction "+IN_3") (pintype "input"))
    )
    (net (code "45") (name "Net-(U2B-+IN)") (class "Default")
      (node (ref "R32") (pin "1") (pinfunction "1_1") (pintype "passive"))
      (node (ref "U2") (pin "10") (pinfunction "+IN_10") (pintype "input"))
      (node (ref "U3") (pin "14") (pinfunction "OUT_14") (pintype "output"))
    )
    (net (code "46") (name "Net-(U2C-+IN)") (class "Default")
      (node (ref "R50") (pin "1") (pinfunction "1_1") (pintype "passive"))
      (node (ref "U2") (pin "5") (pinfunction "+IN_5") (pintype "input"))
      (node (ref "U5") (pin "14") (pinfunction "OUT_14") (pintype "output"))
    )
    (net (code "47") (name "Net-(U3A--IN)") (class "Default")
      (node (ref "R24") (pin "2") (pinfunction "2_2") (pintype "passive"))
      (node (ref "U3") (pin "1") (pinfunction "OUT_1") (pintype "output"))
      (node (ref "U3") (pin "2") (pinfunction "-IN_2") (pintype "input"))
    )
    (net (code "48") (name "Net-(U3B-+IN)") (class "Default")
      (node (ref "C3") (pin "1") (pinfunction "1_1") (pintype "passive"))
      (node (ref "R24") (pin "1") (pinfunction "1_1") (pintype "passive"))
      (node (ref "R25") (pin "2") (pinfunction "2_2") (pintype "passive"))
      (node (ref "U3") (pin "10") (pinfunction "+IN_10") (pintype "input"))
    )
    (net (code "49") (name "Net-(U3B--IN)") (class "Default")
      (node (ref "R30") (pin "1") (pinfunction "1_1") (pintype "passive"))
      (node (ref "R31") (pin "2") (pinfunction "2_2") (pintype "passive"))
      (node (ref "U3") (pin "9") (pinfunction "-IN_9") (pintype "input"))
    )
    (net (code "50") (name "Net-(U3B-OUT)") (class "Default")
      (node (ref "R31") (pin "1") (pinfunction "1_1") (pintype "passive"))
      (node (ref "U3") (pin "5") (pinfunction "+IN_5") (pintype "input"))
      (node (ref "U3") (pin "8") (pinfunction "OUT_8") (pintype "output"))
    )
    (net (code "51") (name "Net-(U3C-OUT)") (class "Default")
      (node (ref "T3") (pin "B") (pinfunction "B_B") (pintype "passive"))
      (node (ref "U3") (pin "7") (pinfunction "OUT_7") (pintype "output"))
    )
    (net (code "52") (name "Net-(U3D-+IN)") (class "Default")
      (node (ref "C4") (pin "1") (pinfunction "1_1") (pintype "passive"))
      (node (ref "R33") (pin "2") (pinfunction "2_2") (pintype "passive"))
      (node (ref "R34") (pin "1") (pinfunction "1_1") (pintype "passive"))
      (node (ref "U3") (pin "12") (pinfunction "+IN_12") (pintype "input"))
    )
    (net (code "53") (name "Net-(U3D--IN)") (class "Default")
      (node (ref "R27") (pin "1") (pinfunction "1_1") (pintype "passive"))
      (node (ref "R32") (pin "2") (pinfunction "2_2") (pintype "passive"))
      (node (ref "U3") (pin "13") (pinfunction "-IN_13") (pintype "input"))
    )
    (net (code "54") (name "Net-(U5A--IN)") (class "Default")
      (node (ref "R42") (pin "2") (pinfunction "2_2") (pintype "passive"))
      (node (ref "U5") (pin "1") (pinfunction "OUT_1") (pintype "output"))
      (node (ref "U5") (pin "2") (pinfunction "-IN_2") (pintype "input"))
    )
    (net (code "55") (name "Net-(U5B-+IN)") (class "Default")
      (node (ref "C5") (pin "1") (pinfunction "1_1") (pintype "passive"))
      (node (ref "R42") (pin "1") (pinfunction "1_1") (pintype "passive"))
      (node (ref "R43") (pin "2") (pinfunction "2_2") (pintype "passive"))
      (node (ref "U5") (pin "10") (pinfunction "+IN_10") (pintype "input"))
    )
    (net (code "56") (name "Net-(U5B--IN)") (class "Default")
      (node (ref "R48") (pin "1") (pinfunction "1_1") (pintype "passive"))
      (node (ref "R49") (pin "2") (pinfunction "2_2") (pintype "passive"))
      (node (ref "U5") (pin "9") (pinfunction "-IN_9") (pintype "input"))
    )
    (net (code "57") (name "Net-(U5B-OUT)") (class "Default")
      (node (ref "R49") (pin "1") (pinfunction "1_1") (pintype "passive"))
      (node (ref "U5") (pin "5") (pinfunction "+IN_5") (pintype "input"))
      (node (ref "U5") (pin "8") (pinfunction "OUT_8") (pintype "output"))
    )
    (net (code "58") (name "Net-(U5C-OUT)") (class "Default")
      (node (ref "T5") (pin "B") (pinfunction "B_B") (pintype "passive"))
      (node (ref "U5") (pin "7") (pinfunction "OUT_7") (pintype "output"))
    )
    (net (code "59") (name "Net-(U5D-+IN)") (class "Default")
      (node (ref "C6") (pin "1") (pinfunction "1_1") (pintype "passive"))
      (node (ref "R51") (pin "2") (pinfunction "2_2") (pintype "passive"))
      (node (ref "R52") (pin "1") (pinfunction "1_1") (pintype "passive"))
      (node (ref "U5") (pin "12") (pinfunction "+IN_12") (pintype "input"))
    )
    (net (code "60") (name "Net-(U5D--IN)") (class "Default")
      (node (ref "R45") (pin "1") (pinfunction "1_1") (pintype "passive"))
      (node (ref "R50") (pin "2") (pinfunction "2_2") (pintype "passive"))
      (node (ref "U5") (pin "13") (pinfunction "-IN_13") (pintype "input"))
    )
  )
)
